# ScoreBoard-0_2.net
KiCad netlist of a schematic drawn in EAGLE
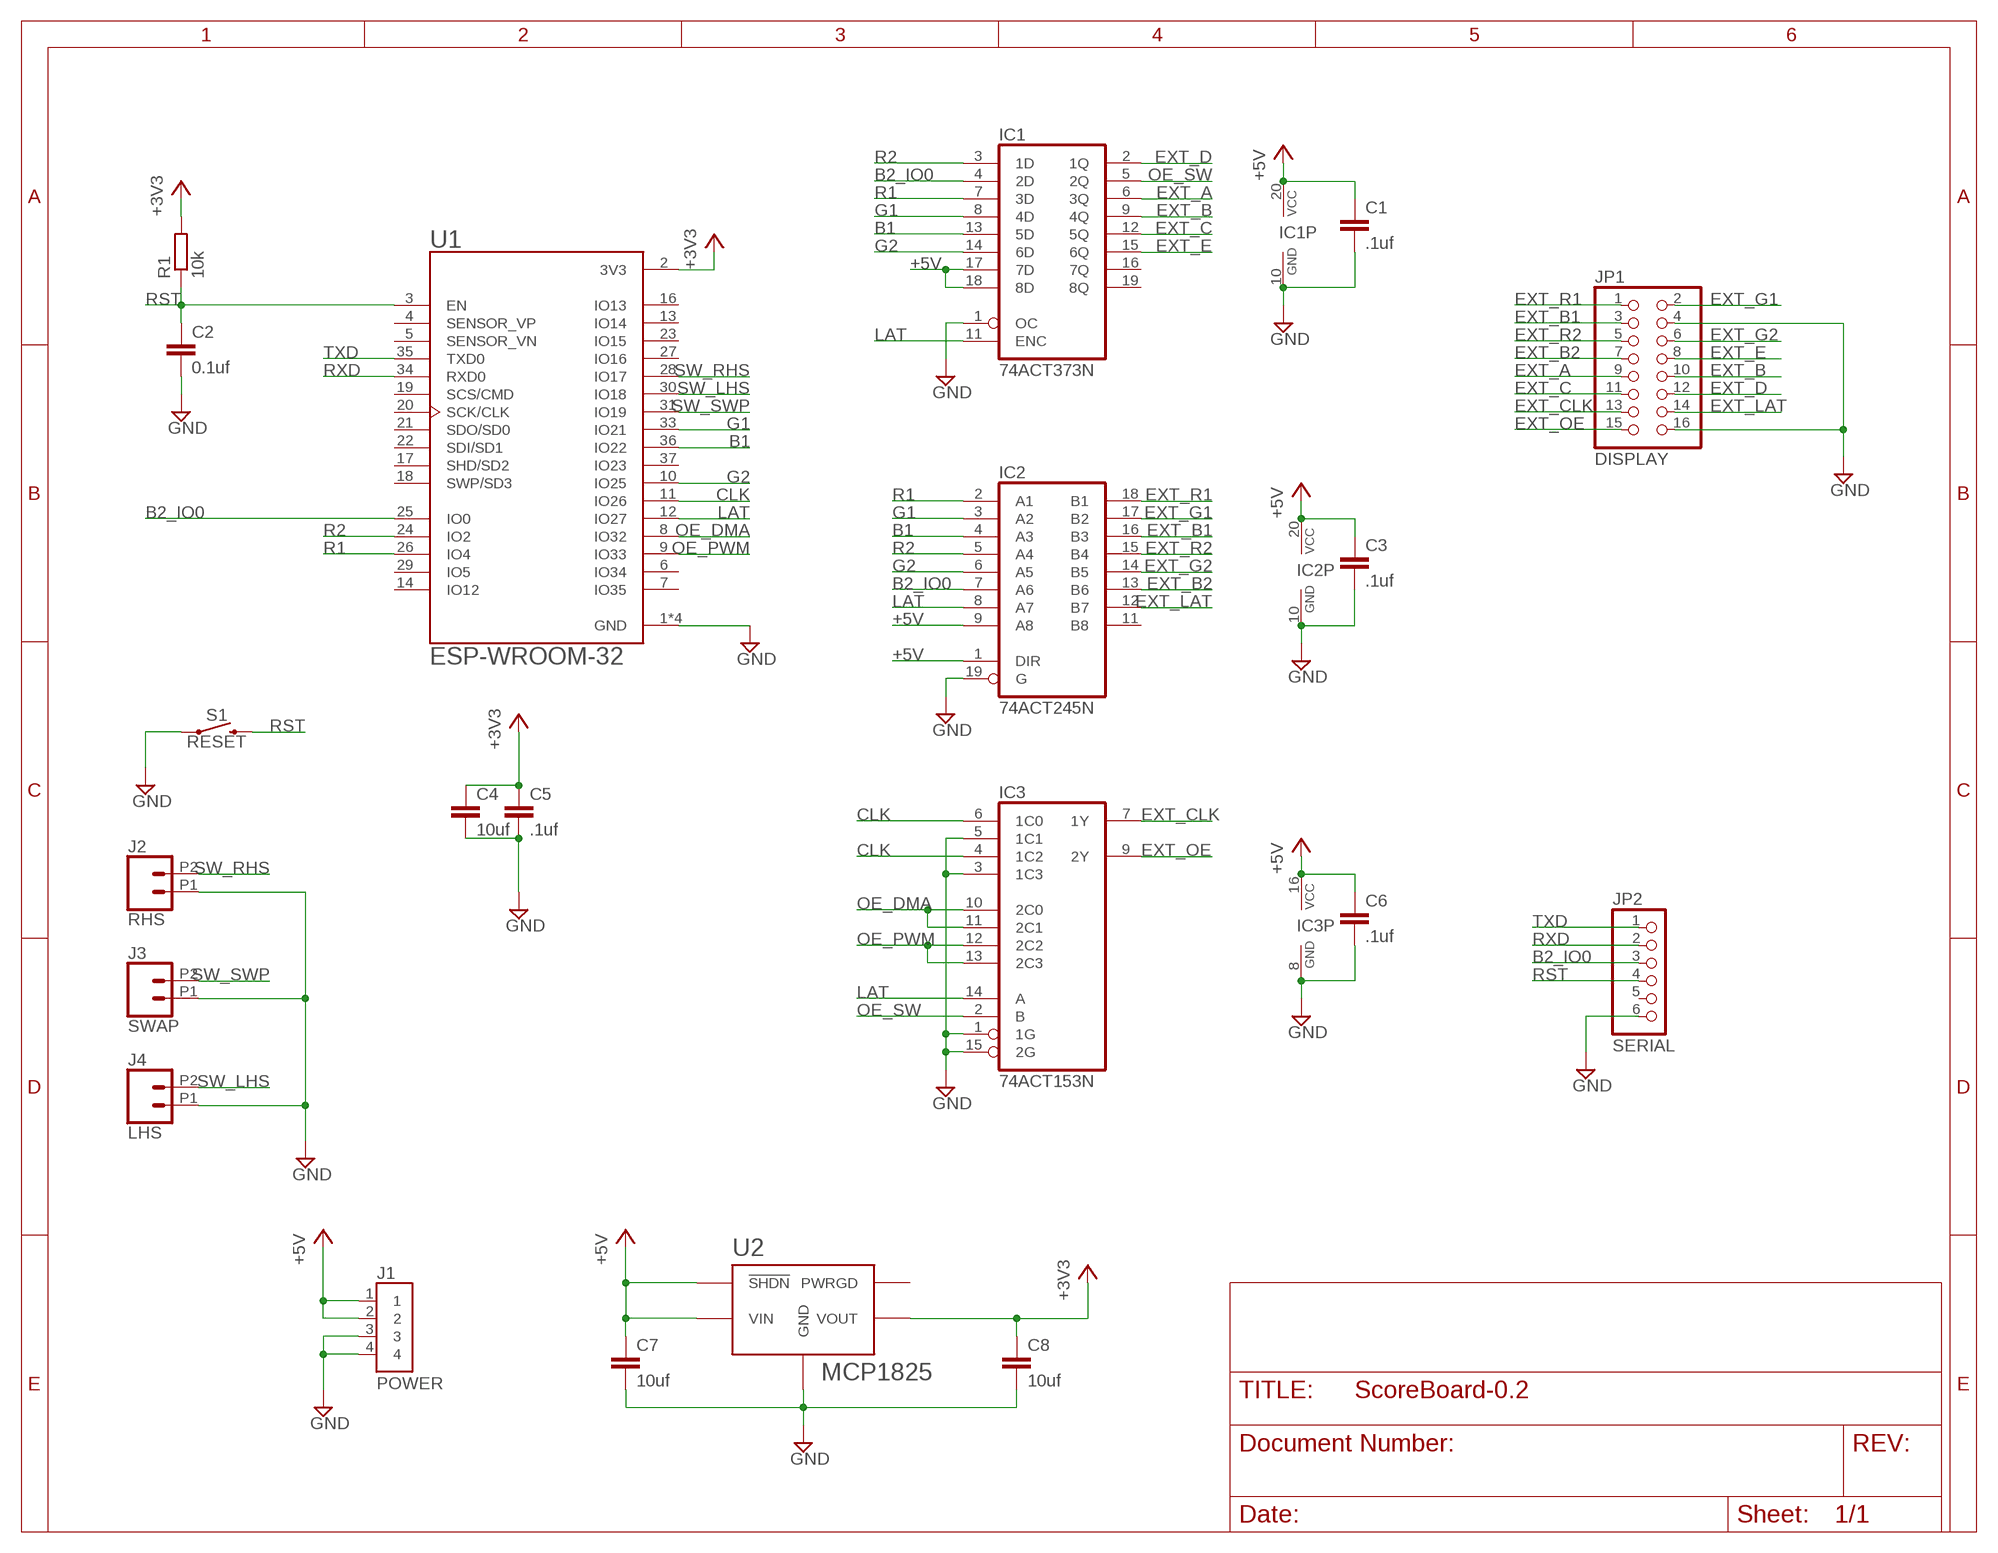
[diagram p0: schematic, sheet 1]

(export (version "E")
  (design (tool "Eeschema 10.0.6"))
  (components
    (comp (ref "C1")
      (value ".1uf")
      (footprint "eagle-import:C025-025X050")
      (libsource (lib "eagle-import") (part "C-EU025-025X050"))
    )
    (comp (ref "C2")
      (value "0.1uf")
      (footprint "eagle-import:C025-025X050")
      (libsource (lib "eagle-import") (part "C-EU025-025X050"))
    )
    (comp (ref "C3")
      (value ".1uf")
      (footprint "eagle-import:C025-025X050")
      (libsource (lib "eagle-import") (part "C-EU025-025X050"))
    )
    (comp (ref "C4")
      (value "10uf")
      (footprint "eagle-import:C050-025X075")
      (libsource (lib "eagle-import") (part "C-EU050-025X075"))
    )
    (comp (ref "C5")
      (value ".1uf")
      (footprint "eagle-import:C025-025X050")
      (libsource (lib "eagle-import") (part "C-EU025-025X050"))
    )
    (comp (ref "C6")
      (value ".1uf")
      (footprint "eagle-import:C025-025X050")
      (libsource (lib "eagle-import") (part "C-EU025-025X050"))
    )
    (comp (ref "C7")
      (value "10uf")
      (footprint "eagle-import:C050-025X075")
      (libsource (lib "eagle-import") (part "C-EU050-025X075"))
    )
    (comp (ref "C8")
      (value "10uf")
      (footprint "eagle-import:C050-025X075")
      (libsource (lib "eagle-import") (part "C-EU050-025X075"))
    )
    (comp (ref "IC1")
      (value "74ACT373N")
      (footprint "eagle-import:DIL20")
      (libsource (lib "eagle-import") (part "74373NACT"))
    )
    (comp (ref "IC2")
      (value "74ACT245N")
      (footprint "eagle-import:DIL20")
      (libsource (lib "eagle-import") (part "74245NACT"))
    )
    (comp (ref "IC3")
      (value "74ACT153N")
      (footprint "eagle-import:DIL16")
      (libsource (lib "eagle-import") (part "74153NACT"))
    )
    (comp (ref "J1")
      (value "POWER")
      (footprint "eagle-import:TE_1-1123723-4")
      (fields
        (field (name "COMMENT") "1-1123723-4")
        (field (name "DIGI-KEY_PART_NUMBER") "A106863-ND")
        (field (name "MF") "TE Connectivity")
      )
      (libsource (lib "eagle-import") (part "1-1123723-4"))
    )
    (comp (ref "J2")
      (value "RHS")
      (footprint "eagle-import:1X02_2.54_SCREWTERM")
      (libsource (lib "eagle-import") (part "CONN_022.54MM_SCREWTERM"))
    )
    (comp (ref "J3")
      (value "SWAP")
      (footprint "eagle-import:1X02_2.54_SCREWTERM")
      (libsource (lib "eagle-import") (part "CONN_022.54MM_SCREWTERM"))
    )
    (comp (ref "J4")
      (value "LHS")
      (footprint "eagle-import:1X02_2.54_SCREWTERM")
      (libsource (lib "eagle-import") (part "CONN_022.54MM_SCREWTERM"))
    )
    (comp (ref "JP1")
      (value "DISPLAY")
      (footprint "eagle-import:2X08")
      (libsource (lib "eagle-import") (part "PINHD-2X8"))
    )
    (comp (ref "JP2")
      (value "SERIAL")
      (footprint "eagle-import:1X06_90")
      (libsource (lib "eagle-import") (part "PINHD-1X6/90"))
    )
    (comp (ref "R1")
      (value "10k")
      (footprint "eagle-import:0204_7")
      (libsource (lib "eagle-import") (part "R-EU_0204/7"))
    )
    (comp (ref "S1")
      (value "RESET")
      (footprint "eagle-import:TACTILE_SWITCH_PTH_6.0MM")
      (libsource (lib "eagle-import") (part "MOMENTARY-SWITCH-SPST-PTH-6.0MM"))
    )
    (comp (ref "U1")
      (value "ESP-WROOM-32")
      (footprint "eagle-import:MODULE_ESP-WROOM-32")
      (fields (field (name "DIGI-KEY_PART_NUMBER") "1188-1178-ND") (field (name "MF") "Olimex LTD"))
      (libsource (lib "eagle-import") (part "ESP-WROOM-32"))
    )
    (comp (ref "U2")
      (value "MCP1825")
      (footprint "eagle-import:SOT-223-5")
      (libsource (lib "eagle-import") (part "MCP1825/DC"))
    )
  )
  (nets
    (net (code "1") (name "+3V3") (class "Default")
      (node (ref "C4") (pin "1") (pinfunction "1_1") (pintype "passive"))
      (node (ref "C5") (pin "1") (pinfunction "1_1") (pintype "passive"))
      (node (ref "C8") (pin "1") (pinfunction "1_1") (pintype "passive"))
      (node (ref "R1") (pin "2") (pinfunction "2_2") (pintype "passive"))
      (node (ref "U1") (pin "2") (pinfunction "3V3_2") (pintype "power_in"))
      (node (ref "U2") (pin "P$4") (pinfunction "VOUT_P$4") (pintype "power_in"))
    )
    (net (code "2") (name "+5V") (class "Default")
      (node (ref "C1") (pin "1") (pinfunction "1_1") (pintype "passive"))
      (node (ref "C3") (pin "1") (pinfunction "1_1") (pintype "passive"))
      (node (ref "C6") (pin "1") (pinfunction "1_1") (pintype "passive"))
      (node (ref "C7") (pin "1") (pinfunction "1_1") (pintype "passive"))
      (node (ref "IC1") (pin "17") (pinfunction "7D_17") (pintype "input"))
      (node (ref "IC1") (pin "18") (pinfunction "8D_18") (pintype "input"))
      (node (ref "IC1") (pin "20") (pinfunction "VCC_20") (pintype "power_in"))
      (node (ref "IC2") (pin "1") (pinfunction "DIR_1") (pintype "input"))
      (node (ref "IC2") (pin "20") (pinfunction "VCC_20") (pintype "power_in"))
      (node (ref "IC2") (pin "9") (pinfunction "A8_9") (pintype "bidirectional"))
      (node (ref "IC3") (pin "16") (pinfunction "VCC_16") (pintype "power_in"))
      (node (ref "J1") (pin "1") (pinfunction "1_1") (pintype "passive"))
      (node (ref "J1") (pin "2") (pinfunction "2_2") (pintype "passive"))
      (node (ref "U2") (pin "P$1") (pinfunction "~{SHDN}_P$1") (pintype "input"))
      (node (ref "U2") (pin "P$2") (pinfunction "VIN_P$2") (pintype "power_in"))
    )
    (net (code "3") (name "/B1") (class "Default")
      (node (ref "IC1") (pin "13") (pinfunction "5D_13") (pintype "input"))
      (node (ref "IC2") (pin "4") (pinfunction "A3_4") (pintype "bidirectional"))
      (node (ref "U1") (pin "36") (pinfunction "IO22_36") (pintype "bidirectional"))
    )
    (net (code "4") (name "/B2_IO0") (class "Default")
      (node (ref "IC1") (pin "4") (pinfunction "2D_4") (pintype "input"))
      (node (ref "IC2") (pin "7") (pinfunction "A6_7") (pintype "bidirectional"))
      (node (ref "JP2") (pin "3") (pinfunction "3_3") (pintype "passive"))
      (node (ref "U1") (pin "25") (pinfunction "IO0_25") (pintype "bidirectional"))
    )
    (net (code "5") (name "/CLK") (class "Default")
      (node (ref "IC3") (pin "4") (pinfunction "1C2_4") (pintype "input"))
      (node (ref "IC3") (pin "6") (pinfunction "1C0_6") (pintype "input"))
      (node (ref "U1") (pin "11") (pinfunction "IO26_11") (pintype "bidirectional"))
    )
    (net (code "6") (name "/EXT_A") (class "Default")
      (node (ref "IC1") (pin "6") (pinfunction "3Q_6") (pintype "tri_state"))
      (node (ref "JP1") (pin "9") (pinfunction "9_9") (pintype "passive"))
    )
    (net (code "7") (name "/EXT_B") (class "Default")
      (node (ref "IC1") (pin "9") (pinfunction "4Q_9") (pintype "tri_state"))
      (node (ref "JP1") (pin "10") (pinfunction "10_10") (pintype "passive"))
    )
    (net (code "8") (name "/EXT_B1") (class "Default")
      (node (ref "IC2") (pin "16") (pinfunction "B3_16") (pintype "bidirectional"))
      (node (ref "JP1") (pin "3") (pinfunction "3_3") (pintype "passive"))
    )
    (net (code "9") (name "/EXT_B2") (class "Default")
      (node (ref "IC2") (pin "13") (pinfunction "B6_13") (pintype "bidirectional"))
      (node (ref "JP1") (pin "7") (pinfunction "7_7") (pintype "passive"))
    )
    (net (code "10") (name "/EXT_C") (class "Default")
      (node (ref "IC1") (pin "12") (pinfunction "5Q_12") (pintype "tri_state"))
      (node (ref "JP1") (pin "11") (pinfunction "11_11") (pintype "passive"))
    )
    (net (code "11") (name "/EXT_CLK") (class "Default")
      (node (ref "IC3") (pin "7") (pinfunction "1Y_7") (pintype "output"))
      (node (ref "JP1") (pin "13") (pinfunction "13_13") (pintype "passive"))
    )
    (net (code "12") (name "/EXT_D") (class "Default")
      (node (ref "IC1") (pin "2") (pinfunction "1Q_2") (pintype "tri_state"))
      (node (ref "JP1") (pin "12") (pinfunction "12_12") (pintype "passive"))
    )
    (net (code "13") (name "/EXT_E") (class "Default")
      (node (ref "IC1") (pin "15") (pinfunction "6Q_15") (pintype "tri_state"))
      (node (ref "JP1") (pin "8") (pinfunction "8_8") (pintype "passive"))
    )
    (net (code "14") (name "/EXT_G1") (class "Default")
      (node (ref "IC2") (pin "17") (pinfunction "B2_17") (pintype "bidirectional"))
      (node (ref "JP1") (pin "2") (pinfunction "2_2") (pintype "passive"))
    )
    (net (code "15") (name "/EXT_G2") (class "Default")
      (node (ref "IC2") (pin "14") (pinfunction "B5_14") (pintype "bidirectional"))
      (node (ref "JP1") (pin "6") (pinfunction "6_6") (pintype "passive"))
    )
    (net (code "16") (name "/EXT_LAT") (class "Default")
      (node (ref "IC2") (pin "12") (pinfunction "B7_12") (pintype "bidirectional"))
      (node (ref "JP1") (pin "14") (pinfunction "14_14") (pintype "passive"))
    )
    (net (code "17") (name "/EXT_OE") (class "Default")
      (node (ref "IC3") (pin "9") (pinfunction "2Y_9") (pintype "output"))
      (node (ref "JP1") (pin "15") (pinfunction "15_15") (pintype "passive"))
    )
    (net (code "18") (name "/EXT_R1") (class "Default")
      (node (ref "IC2") (pin "18") (pinfunction "B1_18") (pintype "bidirectional"))
      (node (ref "JP1") (pin "1") (pinfunction "1_1") (pintype "passive"))
    )
    (net (code "19") (name "/EXT_R2") (class "Default")
      (node (ref "IC2") (pin "15") (pinfunction "B4_15") (pintype "bidirectional"))
      (node (ref "JP1") (pin "5") (pinfunction "5_5") (pintype "passive"))
    )
    (net (code "20") (name "/G1") (class "Default")
      (node (ref "IC1") (pin "8") (pinfunction "4D_8") (pintype "input"))
      (node (ref "IC2") (pin "3") (pinfunction "A2_3") (pintype "bidirectional"))
      (node (ref "U1") (pin "33") (pinfunction "IO21_33") (pintype "bidirectional"))
    )
    (net (code "21") (name "/G2") (class "Default")
      (node (ref "IC1") (pin "14") (pinfunction "6D_14") (pintype "input"))
      (node (ref "IC2") (pin "6") (pinfunction "A5_6") (pintype "bidirectional"))
      (node (ref "U1") (pin "10") (pinfunction "IO25_10") (pintype "bidirectional"))
    )
    (net (code "22") (name "/LAT") (class "Default")
      (node (ref "IC1") (pin "11") (pinfunction "ENC_11") (pintype "input"))
      (node (ref "IC2") (pin "8") (pinfunction "A7_8") (pintype "bidirectional"))
      (node (ref "IC3") (pin "14") (pinfunction "A_14") (pintype "input"))
      (node (ref "U1") (pin "12") (pinfunction "IO27_12") (pintype "bidirectional"))
    )
    (net (code "23") (name "/OE_DMA") (class "Default")
      (node (ref "IC3") (pin "10") (pinfunction "2C0_10") (pintype "input"))
      (node (ref "IC3") (pin "11") (pinfunction "2C1_11") (pintype "input"))
      (node (ref "U1") (pin "8") (pinfunction "IO32_8") (pintype "bidirectional"))
    )
    (net (code "24") (name "/OE_PWM") (class "Default")
      (node (ref "IC3") (pin "12") (pinfunction "2C2_12") (pintype "input"))
      (node (ref "IC3") (pin "13") (pinfunction "2C3_13") (pintype "input"))
      (node (ref "U1") (pin "9") (pinfunction "IO33_9") (pintype "bidirectional"))
    )
    (net (code "25") (name "/OE_SW") (class "Default")
      (node (ref "IC1") (pin "5") (pinfunction "2Q_5") (pintype "tri_state"))
      (node (ref "IC3") (pin "2") (pinfunction "B_2") (pintype "input"))
    )
    (net (code "26") (name "/R1") (class "Default")
      (node (ref "IC1") (pin "7") (pinfunction "3D_7") (pintype "input"))
      (node (ref "IC2") (pin "2") (pinfunction "A1_2") (pintype "bidirectional"))
      (node (ref "U1") (pin "26") (pinfunction "IO4_26") (pintype "bidirectional"))
    )
    (net (code "27") (name "/R2") (class "Default")
      (node (ref "IC1") (pin "3") (pinfunction "1D_3") (pintype "input"))
      (node (ref "IC2") (pin "5") (pinfunction "A4_5") (pintype "bidirectional"))
      (node (ref "U1") (pin "24") (pinfunction "IO2_24") (pintype "bidirectional"))
    )
    (net (code "28") (name "/RST") (class "Default")
      (node (ref "C2") (pin "1") (pinfunction "1_1") (pintype "passive"))
      (node (ref "JP2") (pin "4") (pinfunction "4_4") (pintype "passive"))
      (node (ref "R1") (pin "1") (pinfunction "1_1") (pintype "passive"))
      (node (ref "S1") (pin "3") (pinfunction "2_3") (pintype "passive"))
      (node (ref "U1") (pin "3") (pinfunction "EN_3") (pintype "input"))
    )
    (net (code "29") (name "/RXD") (class "Default")
      (node (ref "JP2") (pin "2") (pinfunction "2_2") (pintype "passive"))
      (node (ref "U1") (pin "34") (pinfunction "RXD0_34") (pintype "bidirectional"))
    )
    (net (code "30") (name "/SW_LHS") (class "Default")
      (node (ref "J4") (pin "P2") (pinfunction "2_P2") (pintype "passive"))
      (node (ref "U1") (pin "30") (pinfunction "IO18_30") (pintype "bidirectional"))
    )
    (net (code "31") (name "/SW_RHS") (class "Default")
      (node (ref "J2") (pin "P2") (pinfunction "2_P2") (pintype "passive"))
      (node (ref "U1") (pin "28") (pinfunction "IO17_28") (pintype "bidirectional"))
    )
    (net (code "32") (name "/SW_SWP") (class "Default")
      (node (ref "J3") (pin "P2") (pinfunction "2_P2") (pintype "passive"))
      (node (ref "U1") (pin "31") (pinfunction "IO19_31") (pintype "bidirectional"))
    )
    (net (code "33") (name "/TXD") (class "Default")
      (node (ref "JP2") (pin "1") (pinfunction "1_1") (pintype "passive"))
      (node (ref "U1") (pin "35") (pinfunction "TXD0_35") (pintype "bidirectional"))
    )
    (net (code "34") (name "GND") (class "Default")
      (node (ref "C1") (pin "2") (pinfunction "2_2") (pintype "passive"))
      (node (ref "C2") (pin "2") (pinfunction "2_2") (pintype "passive"))
      (node (ref "C3") (pin "2") (pinfunction "2_2") (pintype "passive"))
      (node (ref "C4") (pin "2") (pinfunction "2_2") (pintype "passive"))
      (node (ref "C5") (pin "2") (pinfunction "2_2") (pintype "passive"))
      (node (ref "C6") (pin "2") (pinfunction "2_2") (pintype "passive"))
      (node (ref "C7") (pin "2") (pinfunction "2_2") (pintype "passive"))
      (node (ref "C8") (pin "2") (pinfunction "2_2") (pintype "passive"))
      (node (ref "IC1") (pin "1") (pinfunction "OC_1") (pintype "input"))
      (node (ref "IC1") (pin "10") (pinfunction "GND_10") (pintype "power_in"))
      (node (ref "IC2") (pin "10") (pinfunction "GND_10") (pintype "power_in"))
      (node (ref "IC2") (pin "19") (pinfunction "G_19") (pintype "input"))
      (node (ref "IC3") (pin "1") (pinfunction "1G_1") (pintype "input"))
      (node (ref "IC3") (pin "15") (pinfunction "2G_15") (pintype "input"))
      (node (ref "IC3") (pin "3") (pinfunction "1C3_3") (pintype "input"))
      (node (ref "IC3") (pin "5") (pinfunction "1C1_5") (pintype "input"))
      (node (ref "IC3") (pin "8") (pinfunction "GND_8") (pintype "power_in"))
      (node (ref "J1") (pin "3") (pinfunction "3_3") (pintype "passive"))
      (node (ref "J1") (pin "4") (pinfunction "4_4") (pintype "passive"))
      (node (ref "J2") (pin "P1") (pinfunction "1_P1") (pintype "passive"))
      (node (ref "J3") (pin "P1") (pinfunction "1_P1") (pintype "passive"))
      (node (ref "J4") (pin "P1") (pinfunction "1_P1") (pintype "passive"))
      (node (ref "JP1") (pin "16") (pinfunction "16_16") (pintype "passive"))
      (node (ref "JP1") (pin "4") (pinfunction "4_4") (pintype "passive"))
      (node (ref "JP2") (pin "6") (pinfunction "6_6") (pintype "passive"))
      (node (ref "S1") (pin "1") (pinfunction "1_1") (pintype "passive"))
      (node (ref "U1") (pin "1") (pinfunction "GND_1") (pintype "power_in"))
      (node (ref "U1") (pin "1.1") (pinfunction "GND_1.1") (pintype "power_in"))
      (node (ref "U1") (pin "15") (pinfunction "GND_15") (pintype "power_in"))
      (node (ref "U1") (pin "38") (pinfunction "GND_38") (pintype "power_in"))
      (node (ref "U2") (pin "P$3") (pinfunction "GND_P$3") (pintype "power_in"))
      (node (ref "U2") (pin "P$6") (pinfunction "GND_P$6") (pintype "power_in"))
    )
    (net (code "35") (name "unconnected-(IC1A-7Q-Pad16)") (class "Default")
      (node (ref "IC1") (pin "16") (pinfunction "7Q_16") (pintype "tri_state"))
    )
    (net (code "36") (name "unconnected-(IC1A-8Q-Pad19)") (class "Default")
      (node (ref "IC1") (pin "19") (pinfunction "8Q_19") (pintype "tri_state"))
    )
    (net (code "37") (name "unconnected-(IC2A-B8-Pad11)") (class "Default")
      (node (ref "IC2") (pin "11") (pinfunction "B8_11") (pintype "bidirectional"))
    )
    (net (code "38") (name "unconnected-(JP2-Pad5)") (class "Default")
      (node (ref "JP2") (pin "5") (pinfunction "5_5") (pintype "passive"))
    )
    (net (code "39") (name "unconnected-(U1-IO5-Pad29)") (class "Default")
      (node (ref "U1") (pin "29") (pinfunction "IO5_29") (pintype "bidirectional"))
    )
    (net (code "40") (name "unconnected-(U1-IO12-Pad14)") (class "Default")
      (node (ref "U1") (pin "14") (pinfunction "IO12_14") (pintype "bidirectional"))
    )
    (net (code "41") (name "unconnected-(U1-IO13-Pad16)") (class "Default")
      (node (ref "U1") (pin "16") (pinfunction "IO13_16") (pintype "bidirectional"))
    )
    (net (code "42") (name "unconnected-(U1-IO14-Pad13)") (class "Default")
      (node (ref "U1") (pin "13") (pinfunction "IO14_13") (pintype "bidirectional"))
    )
    (net (code "43") (name "unconnected-(U1-IO15-Pad23)") (class "Default")
      (node (ref "U1") (pin "23") (pinfunction "IO15_23") (pintype "bidirectional"))
    )
    (net (code "44") (name "unconnected-(U1-IO16-Pad27)") (class "Default")
      (node (ref "U1") (pin "27") (pinfunction "IO16_27") (pintype "bidirectional"))
    )
    (net (code "45") (name "unconnected-(U1-IO23-Pad37)") (class "Default")
      (node (ref "U1") (pin "37") (pinfunction "IO23_37") (pintype "bidirectional"))
    )
    (net (code "46") (name "unconnected-(U1-IO34-Pad6)") (class "Default")
      (node (ref "U1") (pin "6") (pinfunction "IO34_6") (pintype "bidirectional"))
    )
    (net (code "47") (name "unconnected-(U1-IO35-Pad7)") (class "Default")
      (node (ref "U1") (pin "7") (pinfunction "IO35_7") (pintype "bidirectional"))
    )
    (net (code "48") (name "unconnected-(U1-SCK{slash}CLK-Pad20)") (class "Default")
      (node (ref "U1") (pin "20") (pinfunction "SCK/CLK_20") (pintype "bidirectional"))
    )
    (net (code "49") (name "unconnected-(U1-SCS{slash}CMD-Pad19)") (class "Default")
      (node (ref "U1") (pin "19") (pinfunction "SCS/CMD_19") (pintype "bidirectional"))
    )
    (net (code "50") (name "unconnected-(U1-SDI{slash}SD1-Pad22)") (class "Default")
      (node (ref "U1") (pin "22") (pinfunction "SDI/SD1_22") (pintype "bidirectional"))
    )
    (net (code "51") (name "unconnected-(U1-SDO{slash}SD0-Pad21)") (class "Default")
      (node (ref "U1") (pin "21") (pinfunction "SDO/SD0_21") (pintype "bidirectional"))
    )
    (net (code "52") (name "unconnected-(U1-SENSOR_VN-Pad5)") (class "Default")
      (node (ref "U1") (pin "5") (pinfunction "SENSOR_VN_5") (pintype "input"))
    )
    (net (code "53") (name "unconnected-(U1-SENSOR_VP-Pad4)") (class "Default")
      (node (ref "U1") (pin "4") (pinfunction "SENSOR_VP_4") (pintype "input"))
    )
    (net (code "54") (name "unconnected-(U1-SHD{slash}SD2-Pad17)") (class "Default")
      (node (ref "U1") (pin "17") (pinfunction "SHD/SD2_17") (pintype "bidirectional"))
    )
    (net (code "55") (name "unconnected-(U1-SWP{slash}SD3-Pad18)") (class "Default")
      (node (ref "U1") (pin "18") (pinfunction "SWP/SD3_18") (pintype "bidirectional"))
    )
    (net (code "56") (name "unconnected-(U2-PWRGD-PadP$5)") (class "Default")
      (node (ref "U2") (pin "P$5") (pinfunction "PWRGD_P$5") (pintype "output"))
    )
  )
)
